# STM32-ESP32.net
KiCad netlist of a schematic drawn in EasyEDA Pro
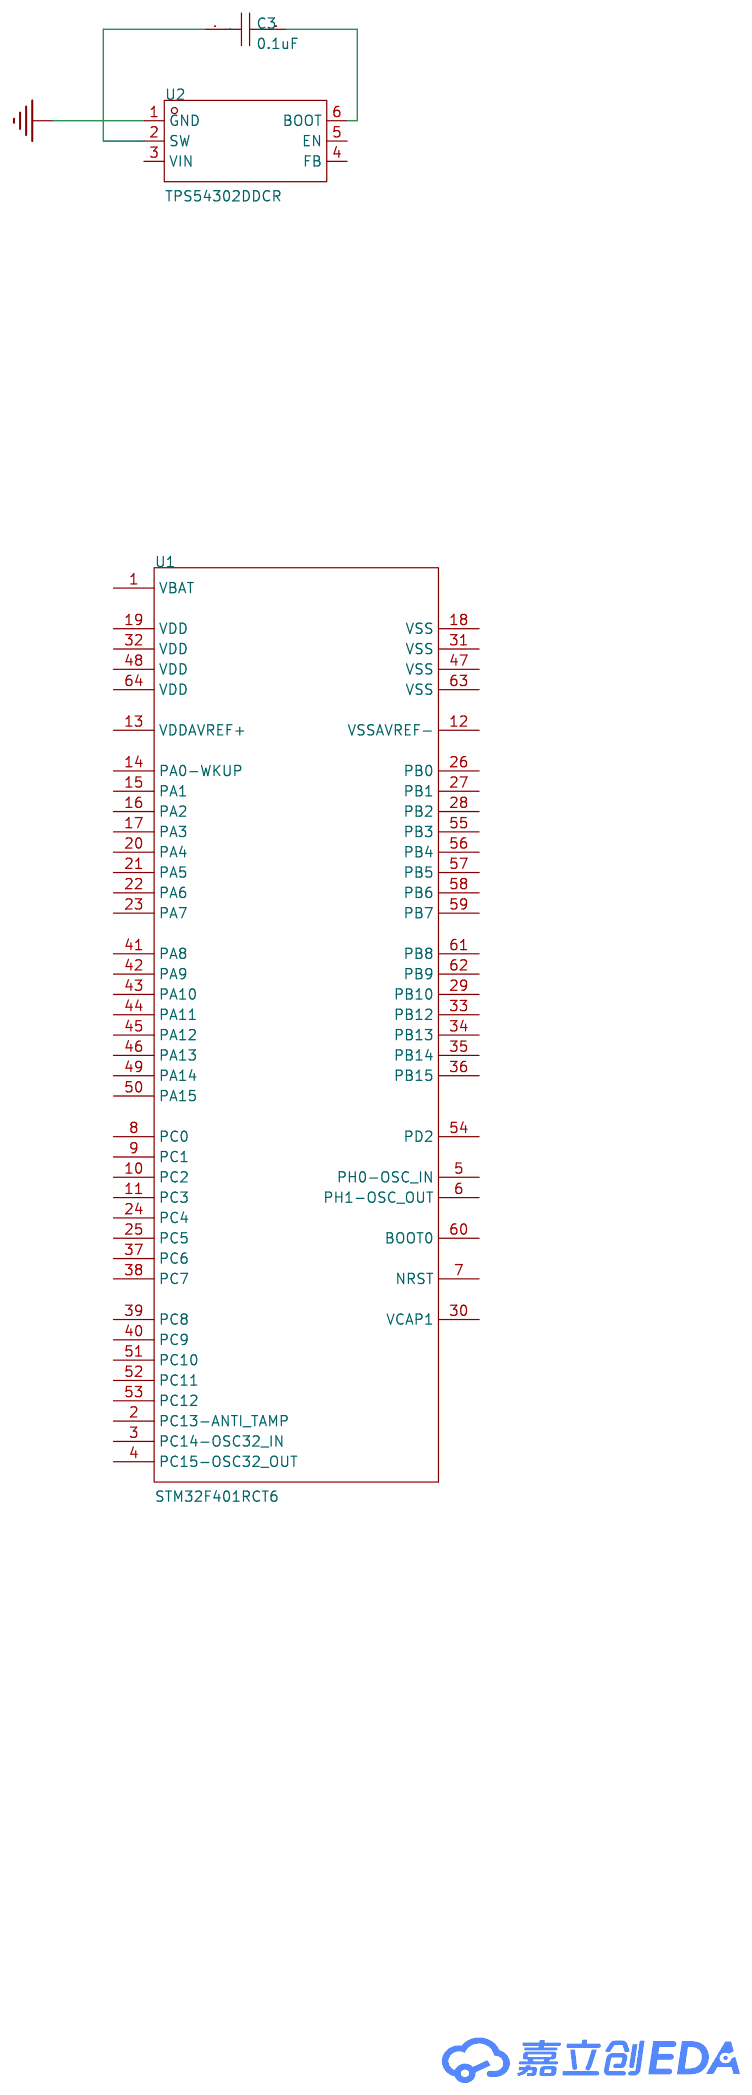
[diagram p0: schematic sheet]

(export (version "E")
  (design (tool "Eeschema 10.0.6"))
  (components
    (comp (ref "C3")
      (value "0.1uF")
      (footprint "easyedapro:C0603")
      (libsource (lib "easyedapro") (part "CapAcitance"))
    )
    (comp (ref "U1")
      (value "STM32F401RCT6")
      (footprint "easyedapro:LQFP-64_L10.0-W10.0-P0.50-LS12.0-BL")
      (description "CPU内核:ARM-M4;程序存储容量:256KB;RAM总容量:64KB;GPIO端口数量:50;工作电压范围:1.7V~3.6V;CPU最大主频:84MHz;程序存储器类型:FLASH;")
      (fields (field (name "Manufacturer") "ST(意法半导体)"))
      (libsource (lib "easyedapro") (part "STM32F401RCT6"))
    )
    (comp (ref "U2")
      (value "TPS54302DDCR")
      (footprint "easyedapro:SOT-23-6_L2.9-W1.6-P0.95-LS2.8-BL")
      (description "功能类型:降压型;输出类型:固定;工作电压:4.5V~28V;输出电压:5V;输出电流:3A;")
      (fields (field (name "Manufacturer") "TI(德州仪器)"))
      (libsource (lib "easyedapro") (part "TPS54302DDCR_C311983"))
    )
  )
  (nets
    (net (code "1") (name "GND") (class "Default")
      (node (ref "U2") (pin "1") (pinfunction "GND_1") (pintype "unspecified"))
    )
    (net (code "2") (name "Net-(U2-BOOT)") (class "Default")
      (node (ref "C3") (pin "2") (pinfunction "2_2") (pintype "input"))
      (node (ref "U2") (pin "6") (pinfunction "BOOT_6") (pintype "unspecified"))
    )
    (net (code "3") (name "Net-(U2-SW)") (class "Default")
      (node (ref "C3") (pin "1") (pinfunction "1_1") (pintype "input"))
      (node (ref "U2") (pin "2") (pinfunction "SW_2") (pintype "unspecified"))
    )
    (net (code "4") (name "unconnected-(U1-BOOT0-Pad60)") (class "Default")
      (node (ref "U1") (pin "60") (pinfunction "BOOT0_60") (pintype "unspecified"))
    )
    (net (code "5") (name "unconnected-(U1-NRST-Pad7)") (class "Default")
      (node (ref "U1") (pin "7") (pinfunction "NRST_7") (pintype "bidirectional"))
    )
    (net (code "6") (name "unconnected-(U1-PA0-WKUP-Pad14)") (class "Default")
      (node (ref "U1") (pin "14") (pinfunction "PA0-WKUP_14") (pintype "bidirectional"))
    )
    (net (code "7") (name "unconnected-(U1-PA1-Pad15)") (class "Default")
      (node (ref "U1") (pin "15") (pinfunction "PA1_15") (pintype "bidirectional"))
    )
    (net (code "8") (name "unconnected-(U1-PA2-Pad16)") (class "Default")
      (node (ref "U1") (pin "16") (pinfunction "PA2_16") (pintype "bidirectional"))
    )
    (net (code "9") (name "unconnected-(U1-PA3-Pad17)") (class "Default")
      (node (ref "U1") (pin "17") (pinfunction "PA3_17") (pintype "bidirectional"))
    )
    (net (code "10") (name "unconnected-(U1-PA4-Pad20)") (class "Default")
      (node (ref "U1") (pin "20") (pinfunction "PA4_20") (pintype "bidirectional"))
    )
    (net (code "11") (name "unconnected-(U1-PA5-Pad21)") (class "Default")
      (node (ref "U1") (pin "21") (pinfunction "PA5_21") (pintype "bidirectional"))
    )
    (net (code "12") (name "unconnected-(U1-PA6-Pad22)") (class "Default")
      (node (ref "U1") (pin "22") (pinfunction "PA6_22") (pintype "bidirectional"))
    )
    (net (code "13") (name "unconnected-(U1-PA7-Pad23)") (class "Default")
      (node (ref "U1") (pin "23") (pinfunction "PA7_23") (pintype "bidirectional"))
    )
    (net (code "14") (name "unconnected-(U1-PA8-Pad41)") (class "Default")
      (node (ref "U1") (pin "41") (pinfunction "PA8_41") (pintype "bidirectional"))
    )
    (net (code "15") (name "unconnected-(U1-PA9-Pad42)") (class "Default")
      (node (ref "U1") (pin "42") (pinfunction "PA9_42") (pintype "bidirectional"))
    )
    (net (code "16") (name "unconnected-(U1-PA10-Pad43)") (class "Default")
      (node (ref "U1") (pin "43") (pinfunction "PA10_43") (pintype "bidirectional"))
    )
    (net (code "17") (name "unconnected-(U1-PA11-Pad44)") (class "Default")
      (node (ref "U1") (pin "44") (pinfunction "PA11_44") (pintype "bidirectional"))
    )
    (net (code "18") (name "unconnected-(U1-PA12-Pad45)") (class "Default")
      (node (ref "U1") (pin "45") (pinfunction "PA12_45") (pintype "bidirectional"))
    )
    (net (code "19") (name "unconnected-(U1-PA13-Pad46)") (class "Default")
      (node (ref "U1") (pin "46") (pinfunction "PA13_46") (pintype "bidirectional"))
    )
    (net (code "20") (name "unconnected-(U1-PA14-Pad49)") (class "Default")
      (node (ref "U1") (pin "49") (pinfunction "PA14_49") (pintype "bidirectional"))
    )
    (net (code "21") (name "unconnected-(U1-PA15-Pad50)") (class "Default")
      (node (ref "U1") (pin "50") (pinfunction "PA15_50") (pintype "bidirectional"))
    )
    (net (code "22") (name "unconnected-(U1-PB0-Pad26)") (class "Default")
      (node (ref "U1") (pin "26") (pinfunction "PB0_26") (pintype "bidirectional"))
    )
    (net (code "23") (name "unconnected-(U1-PB1-Pad27)") (class "Default")
      (node (ref "U1") (pin "27") (pinfunction "PB1_27") (pintype "bidirectional"))
    )
    (net (code "24") (name "unconnected-(U1-PB2-Pad28)") (class "Default")
      (node (ref "U1") (pin "28") (pinfunction "PB2_28") (pintype "bidirectional"))
    )
    (net (code "25") (name "unconnected-(U1-PB3-Pad55)") (class "Default")
      (node (ref "U1") (pin "55") (pinfunction "PB3_55") (pintype "bidirectional"))
    )
    (net (code "26") (name "unconnected-(U1-PB4-Pad56)") (class "Default")
      (node (ref "U1") (pin "56") (pinfunction "PB4_56") (pintype "bidirectional"))
    )
    (net (code "27") (name "unconnected-(U1-PB5-Pad57)") (class "Default")
      (node (ref "U1") (pin "57") (pinfunction "PB5_57") (pintype "bidirectional"))
    )
    (net (code "28") (name "unconnected-(U1-PB6-Pad58)") (class "Default")
      (node (ref "U1") (pin "58") (pinfunction "PB6_58") (pintype "bidirectional"))
    )
    (net (code "29") (name "unconnected-(U1-PB7-Pad59)") (class "Default")
      (node (ref "U1") (pin "59") (pinfunction "PB7_59") (pintype "bidirectional"))
    )
    (net (code "30") (name "unconnected-(U1-PB8-Pad61)") (class "Default")
      (node (ref "U1") (pin "61") (pinfunction "PB8_61") (pintype "bidirectional"))
    )
    (net (code "31") (name "unconnected-(U1-PB9-Pad62)") (class "Default")
      (node (ref "U1") (pin "62") (pinfunction "PB9_62") (pintype "bidirectional"))
    )
    (net (code "32") (name "unconnected-(U1-PB10-Pad29)") (class "Default")
      (node (ref "U1") (pin "29") (pinfunction "PB10_29") (pintype "bidirectional"))
    )
    (net (code "33") (name "unconnected-(U1-PB12-Pad33)") (class "Default")
      (node (ref "U1") (pin "33") (pinfunction "PB12_33") (pintype "bidirectional"))
    )
    (net (code "34") (name "unconnected-(U1-PB13-Pad34)") (class "Default")
      (node (ref "U1") (pin "34") (pinfunction "PB13_34") (pintype "bidirectional"))
    )
    (net (code "35") (name "unconnected-(U1-PB14-Pad35)") (class "Default")
      (node (ref "U1") (pin "35") (pinfunction "PB14_35") (pintype "bidirectional"))
    )
    (net (code "36") (name "unconnected-(U1-PB15-Pad36)") (class "Default")
      (node (ref "U1") (pin "36") (pinfunction "PB15_36") (pintype "bidirectional"))
    )
    (net (code "37") (name "unconnected-(U1-PC0-Pad8)") (class "Default")
      (node (ref "U1") (pin "8") (pinfunction "PC0_8") (pintype "bidirectional"))
    )
    (net (code "38") (name "unconnected-(U1-PC1-Pad9)") (class "Default")
      (node (ref "U1") (pin "9") (pinfunction "PC1_9") (pintype "bidirectional"))
    )
    (net (code "39") (name "unconnected-(U1-PC2-Pad10)") (class "Default")
      (node (ref "U1") (pin "10") (pinfunction "PC2_10") (pintype "bidirectional"))
    )
    (net (code "40") (name "unconnected-(U1-PC3-Pad11)") (class "Default")
      (node (ref "U1") (pin "11") (pinfunction "PC3_11") (pintype "bidirectional"))
    )
    (net (code "41") (name "unconnected-(U1-PC4-Pad24)") (class "Default")
      (node (ref "U1") (pin "24") (pinfunction "PC4_24") (pintype "bidirectional"))
    )
    (net (code "42") (name "unconnected-(U1-PC5-Pad25)") (class "Default")
      (node (ref "U1") (pin "25") (pinfunction "PC5_25") (pintype "bidirectional"))
    )
    (net (code "43") (name "unconnected-(U1-PC6-Pad37)") (class "Default")
      (node (ref "U1") (pin "37") (pinfunction "PC6_37") (pintype "bidirectional"))
    )
    (net (code "44") (name "unconnected-(U1-PC7-Pad38)") (class "Default")
      (node (ref "U1") (pin "38") (pinfunction "PC7_38") (pintype "bidirectional"))
    )
    (net (code "45") (name "unconnected-(U1-PC8-Pad39)") (class "Default")
      (node (ref "U1") (pin "39") (pinfunction "PC8_39") (pintype "bidirectional"))
    )
    (net (code "46") (name "unconnected-(U1-PC9-Pad40)") (class "Default")
      (node (ref "U1") (pin "40") (pinfunction "PC9_40") (pintype "bidirectional"))
    )
    (net (code "47") (name "unconnected-(U1-PC10-Pad51)") (class "Default")
      (node (ref "U1") (pin "51") (pinfunction "PC10_51") (pintype "bidirectional"))
    )
    (net (code "48") (name "unconnected-(U1-PC11-Pad52)") (class "Default")
      (node (ref "U1") (pin "52") (pinfunction "PC11_52") (pintype "bidirectional"))
    )
    (net (code "49") (name "unconnected-(U1-PC12-Pad53)") (class "Default")
      (node (ref "U1") (pin "53") (pinfunction "PC12_53") (pintype "bidirectional"))
    )
    (net (code "50") (name "unconnected-(U1-PC13-ANTI_TAMP-Pad2)") (class "Default")
      (node (ref "U1") (pin "2") (pinfunction "PC13-ANTI_TAMP_2") (pintype "bidirectional"))
    )
    (net (code "51") (name "unconnected-(U1-PC14-OSC32_IN-Pad3)") (class "Default")
      (node (ref "U1") (pin "3") (pinfunction "PC14-OSC32_IN_3") (pintype "bidirectional"))
    )
    (net (code "52") (name "unconnected-(U1-PC15-OSC32_OUT-Pad4)") (class "Default")
      (node (ref "U1") (pin "4") (pinfunction "PC15-OSC32_OUT_4") (pintype "bidirectional"))
    )
    (net (code "53") (name "unconnected-(U1-PD2-Pad54)") (class "Default")
      (node (ref "U1") (pin "54") (pinfunction "PD2_54") (pintype "bidirectional"))
    )
    (net (code "54") (name "unconnected-(U1-PH0-OSC_IN-Pad5)") (class "Default")
      (node (ref "U1") (pin "5") (pinfunction "PH0-OSC_IN_5") (pintype "bidirectional"))
    )
    (net (code "55") (name "unconnected-(U1-PH1-OSC_OUT-Pad6)") (class "Default")
      (node (ref "U1") (pin "6") (pinfunction "PH1-OSC_OUT_6") (pintype "bidirectional"))
    )
    (net (code "56") (name "unconnected-(U1-VBAT-Pad1)") (class "Default")
      (node (ref "U1") (pin "1") (pinfunction "VBAT_1") (pintype "unspecified"))
    )
    (net (code "57") (name "unconnected-(U1-VCAP1-Pad30)") (class "Default")
      (node (ref "U1") (pin "30") (pinfunction "VCAP1_30") (pintype "unspecified"))
    )
    (net (code "58") (name "unconnected-(U1-VDD-Pad19)") (class "Default")
      (node (ref "U1") (pin "19") (pinfunction "VDD_19") (pintype "unspecified"))
    )
    (net (code "59") (name "unconnected-(U1-VDD-Pad32)") (class "Default")
      (node (ref "U1") (pin "32") (pinfunction "VDD_32") (pintype "unspecified"))
    )
    (net (code "60") (name "unconnected-(U1-VDD-Pad48)") (class "Default")
      (node (ref "U1") (pin "48") (pinfunction "VDD_48") (pintype "unspecified"))
    )
    (net (code "61") (name "unconnected-(U1-VDD-Pad64)") (class "Default")
      (node (ref "U1") (pin "64") (pinfunction "VDD_64") (pintype "unspecified"))
    )
    (net (code "62") (name "unconnected-(U1-VDDAVREF+-Pad13)") (class "Default")
      (node (ref "U1") (pin "13") (pinfunction "VDDAVREF+_13") (pintype "unspecified"))
    )
    (net (code "63") (name "unconnected-(U1-VSS-Pad18)") (class "Default")
      (node (ref "U1") (pin "18") (pinfunction "VSS_18") (pintype "unspecified"))
    )
    (net (code "64") (name "unconnected-(U1-VSS-Pad31)") (class "Default")
      (node (ref "U1") (pin "31") (pinfunction "VSS_31") (pintype "unspecified"))
    )
    (net (code "65") (name "unconnected-(U1-VSS-Pad47)") (class "Default")
      (node (ref "U1") (pin "47") (pinfunction "VSS_47") (pintype "unspecified"))
    )
    (net (code "66") (name "unconnected-(U1-VSS-Pad63)") (class "Default")
      (node (ref "U1") (pin "63") (pinfunction "VSS_63") (pintype "unspecified"))
    )
    (net (code "67") (name "unconnected-(U1-VSSAVREF--Pad12)") (class "Default")
      (node (ref "U1") (pin "12") (pinfunction "VSSAVREF-_12") (pintype "unspecified"))
    )
    (net (code "68") (name "unconnected-(U2-EN-Pad5)") (class "Default")
      (node (ref "U2") (pin "5") (pinfunction "EN_5") (pintype "unspecified"))
    )
    (net (code "69") (name "unconnected-(U2-FB-Pad4)") (class "Default")
      (node (ref "U2") (pin "4") (pinfunction "FB_4") (pintype "unspecified"))
    )
    (net (code "70") (name "unconnected-(U2-VIN-Pad3)") (class "Default")
      (node (ref "U2") (pin "3") (pinfunction "VIN_3") (pintype "unspecified"))
    )
  )
)
